# main.net
KiCad netlist of a schematic drawn in Altium Designer
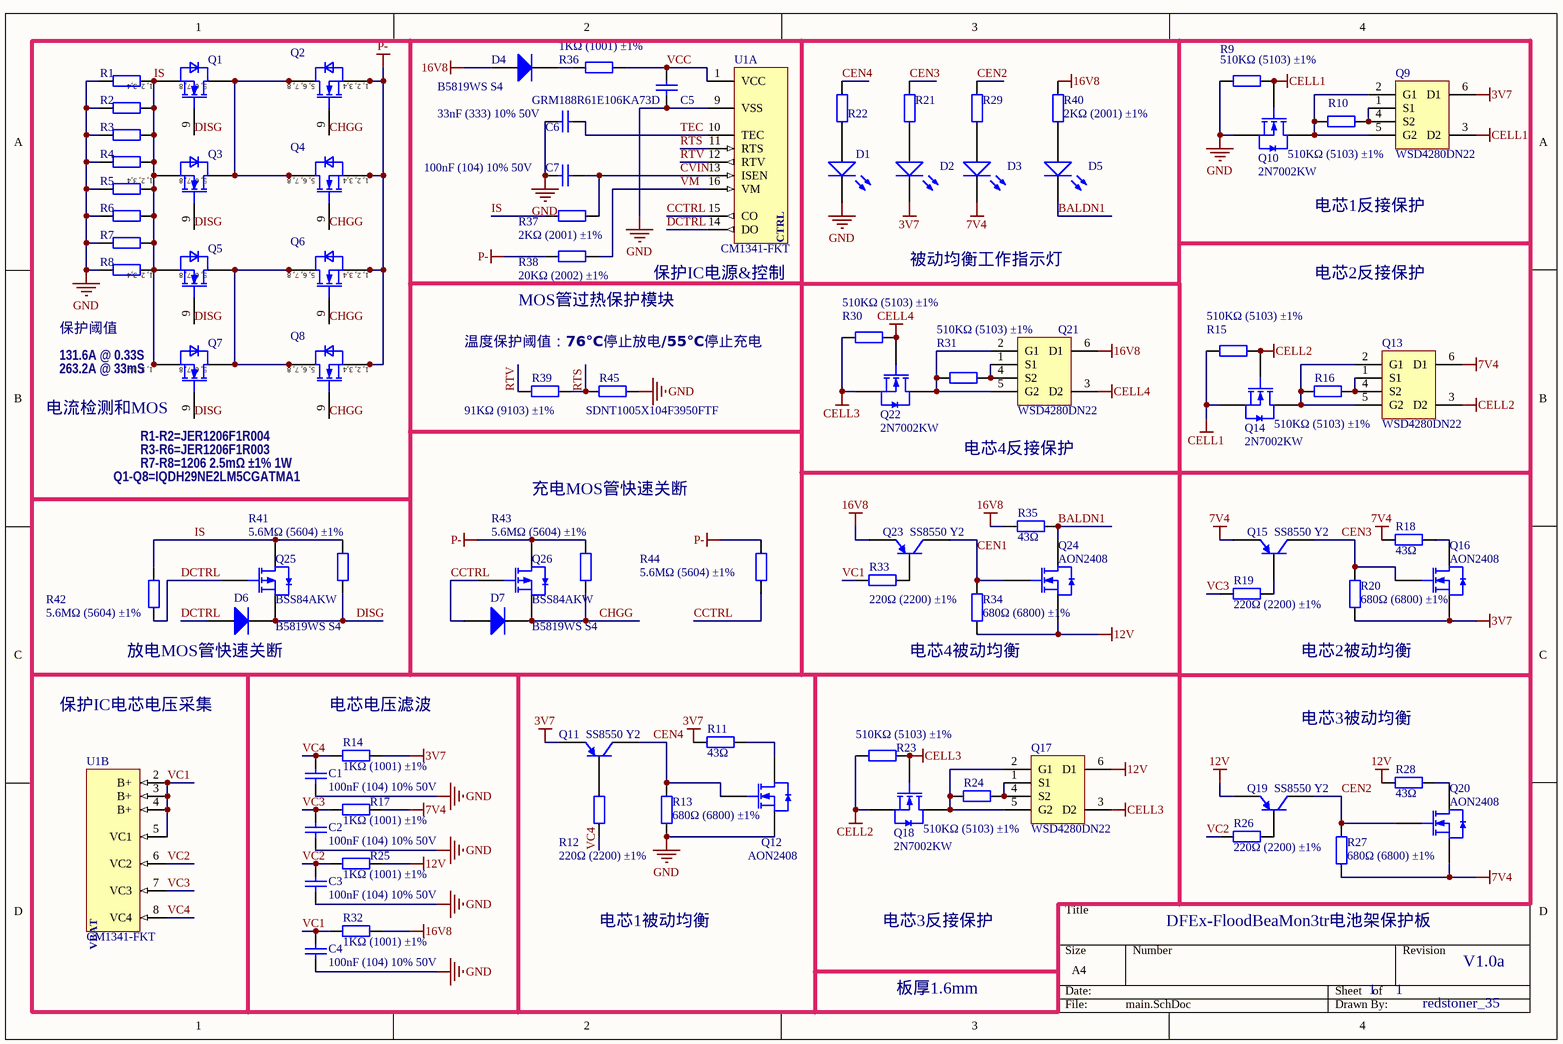
[diagram p0: main.SchDoc]

(export (version "E")
  (design (tool "Eeschema 10.0.6"))
  (components
    (comp (ref "C1")
      (value "100nF (104) 10% 50V")
      (footprint "0402_C")
      (description "贴片电容")
      (libsource (lib "Miscellaneous Devices LC") (part "0402 220nF (224) 10% 16V"))
    )
    (comp (ref "C2")
      (value "100nF (104) 10% 50V")
      (footprint "0402_C")
      (description "贴片电容")
      (libsource (lib "Miscellaneous Devices LC") (part "0402 220nF (224) 10% 16V"))
    )
    (comp (ref "C3")
      (value "100nF (104) 10% 50V")
      (footprint "0402_C")
      (description "贴片电容")
      (libsource (lib "Miscellaneous Devices LC") (part "0402 220nF (224) 10% 16V"))
    )
    (comp (ref "C4")
      (value "100nF (104) 10% 50V")
      (footprint "0402_C")
      (description "贴片电容")
      (libsource (lib "Miscellaneous Devices LC") (part "0402 220nF (224) 10% 16V"))
    )
    (comp (ref "C5")
      (value "GRM188R61E106KA73D")
      (footprint "0603_C")
      (description "0603贴片MLCC电容 10uF ±20% 25V X5R")
      (libsource (lib "Miscellaneous Devices LC") (part "0603 10uF (106) 10% 10V"))
    )
    (comp (ref "C6")
      (value "33nF (333) 10% 50V")
      (footprint "0402_C")
      (description "贴片电容")
      (libsource (lib "Miscellaneous Devices LC") (part "0402 100nF (104) 10% 16V"))
    )
    (comp (ref "C7")
      (value "100nF (104) 10% 50V")
      (footprint "0402_C")
      (description "贴片电容")
      (libsource (lib "Miscellaneous Devices LC") (part "0402 100nF (104) 10% 16V"))
    )
    (comp (ref "D1")
      (value "白灯 0603")
      (footprint "0603_LED_S1")
      (description "发光二极管")
      (libsource (lib "Miscellaneous Devices LC") (part "0603 白灯"))
    )
    (comp (ref "D2")
      (value "白灯 0603")
      (footprint "0603_LED_S1")
      (description "发光二极管")
      (libsource (lib "Miscellaneous Devices LC") (part "0603 白灯"))
    )
    (comp (ref "D3")
      (value "白灯 0603")
      (footprint "0603_LED_S1")
      (description "发光二极管")
      (libsource (lib "Miscellaneous Devices LC") (part "0603 白灯"))
    )
    (comp (ref "D4")
      (value "B5819WS S4")
      (footprint "SOD-323")
      (description "二极管")
      (libsource (lib "Miscellaneous Devices LC") (part "SOD-323 1N4148WS T4"))
    )
    (comp (ref "D5")
      (value "白灯 0603")
      (footprint "0603_LED_S1")
      (description "发光二极管")
      (libsource (lib "Miscellaneous Devices LC") (part "0603 白灯"))
    )
    (comp (ref "D6")
      (value "B5819WS S4")
      (footprint "SOD-323")
      (description "二极管")
      (libsource (lib "Miscellaneous Devices LC") (part "SOD-323 1N4148WS T4"))
    )
    (comp (ref "D7")
      (value "B5819WS S4")
      (footprint "SOD-323")
      (description "二极管")
      (libsource (lib "Miscellaneous Devices LC") (part "SOD-323 1N4148WS T4"))
    )
    (comp (ref "Q1")
      (value "IQDH29NE2LM5CG")
      (footprint "IFX-PG-WHTFN-9-2-V")
      (description "英飞凌MOSFET 25V 789A 0.2mΩ @ 10V WHTFN-9(PDFN5x6源极底置)封装")
      (fields (field (name "MANUFACTURER") "Infineon Technologies"))
      (libsource (lib "custom") (part "IQDH29NE2LM5CGSC"))
    )
    (comp (ref "Q2")
      (value "IQDH29NE2LM5CG")
      (footprint "IFX-PG-WHTFN-9-2-V")
      (description "英飞凌MOSFET 25V 789A 0.2mΩ @ 10V WHTFN-9(PDFN5x6源极底置)封装")
      (fields (field (name "MANUFACTURER") "Infineon Technologies"))
      (libsource (lib "custom") (part "IQDH29NE2LM5CGSC"))
    )
    (comp (ref "Q3")
      (value "IQDH29NE2LM5CG")
      (footprint "IFX-PG-WHTFN-9-2-V")
      (description "英飞凌MOSFET 25V 789A 0.2mΩ @ 10V WHTFN-9(PDFN5x6源极底置)封装")
      (fields (field (name "MANUFACTURER") "Infineon Technologies"))
      (libsource (lib "custom") (part "IQDH29NE2LM5CGSC"))
    )
    (comp (ref "Q4")
      (value "IQDH29NE2LM5CG")
      (footprint "IFX-PG-WHTFN-9-2-V")
      (description "英飞凌MOSFET 25V 789A 0.2mΩ @ 10V WHTFN-9(PDFN5x6源极底置)封装")
      (fields (field (name "MANUFACTURER") "Infineon Technologies"))
      (libsource (lib "custom") (part "IQDH29NE2LM5CGSC"))
    )
    (comp (ref "Q5")
      (value "IQDH29NE2LM5CG")
      (footprint "IFX-PG-WHTFN-9-2-V")
      (description "英飞凌MOSFET 25V 789A 0.2mΩ @ 10V WHTFN-9(PDFN5x6源极底置)封装")
      (fields (field (name "MANUFACTURER") "Infineon Technologies"))
      (libsource (lib "custom") (part "IQDH29NE2LM5CGSC"))
    )
    (comp (ref "Q6")
      (value "IQDH29NE2LM5CG")
      (footprint "IFX-PG-WHTFN-9-2-V")
      (description "英飞凌MOSFET 25V 789A 0.2mΩ @ 10V WHTFN-9(PDFN5x6源极底置)封装")
      (fields (field (name "MANUFACTURER") "Infineon Technologies"))
      (libsource (lib "custom") (part "IQDH29NE2LM5CGSC"))
    )
    (comp (ref "Q7")
      (value "IQDH29NE2LM5CG")
      (footprint "IFX-PG-WHTFN-9-2-V")
      (description "英飞凌MOSFET 25V 789A 0.2mΩ @ 10V WHTFN-9(PDFN5x6源极底置)封装")
      (fields (field (name "MANUFACTURER") "Infineon Technologies"))
      (libsource (lib "custom") (part "IQDH29NE2LM5CGSC"))
    )
    (comp (ref "Q8")
      (value "IQDH29NE2LM5CG")
      (footprint "IFX-PG-WHTFN-9-2-V")
      (description "英飞凌MOSFET 25V 789A 0.2mΩ @ 10V WHTFN-9(PDFN5x6源极底置)封装")
      (fields (field (name "MANUFACTURER") "Infineon Technologies"))
      (libsource (lib "custom") (part "IQDH29NE2LM5CGSC"))
    )
    (comp (ref "Q9")
      (value "WSD4280DN22")
      (footprint "UDFN-6_L2.0-W2.0-P0.65-BL_NTLUD3A50PZ")
      (description "内置肖特基二极管的双P沟道MOS -15V -4.6A 45mΩ @ 4.5V DFN2x2封装")
      (libsource (lib "custom") (part "NTLUD3A50PZ"))
    )
    (comp (ref "Q10")
      (value "2N7002KW")
      (footprint "SC70-3")
      (description "单N沟道MOSFET(场效应管)")
      (libsource (lib "Miscellaneous Devices LC") (part "2N7002 7002"))
    )
    (comp (ref "Q11")
      (value "SS8550 Y2")
      (footprint "SC70-3")
      (description "PNP三极管，SOT-323 封装")
      (libsource (lib "Miscellaneous Devices LC") (part "SOT-23 SS8550 Y2"))
    )
    (comp (ref "Q12")
      (value "AON2408")
      (footprint "PDFN-6_L2.0-W2.0-P0.65-BL-EP")
      (description "MOS(场效应管)")
      (libsource (lib "Miscellaneous Devices LC") (part "AO3400A N道沟 X0YV1T SOT-23"))
    )
    (comp (ref "Q13")
      (value "WSD4280DN22")
      (footprint "UDFN-6_L2.0-W2.0-P0.65-BL_NTLUD3A50PZ")
      (description "内置肖特基二极管的双P沟道MOS -15V -4.6A 45mΩ @ 4.5V DFN2x2封装")
      (libsource (lib "custom") (part "NTLUD3A50PZ"))
    )
    (comp (ref "Q14")
      (value "2N7002KW")
      (footprint "SC70-3")
      (description "单N沟道MOSFET(场效应管)")
      (libsource (lib "Miscellaneous Devices LC") (part "2N7002 7002"))
    )
    (comp (ref "Q15")
      (value "SS8550 Y2")
      (footprint "SC70-3")
      (description "PNP三极管，SOT-323 封装")
      (libsource (lib "Miscellaneous Devices LC") (part "SOT-23 SS8550 Y2"))
    )
    (comp (ref "Q16")
      (value "AON2408")
      (footprint "PDFN-6_L2.0-W2.0-P0.65-BL-EP")
      (description "MOS(场效应管)")
      (libsource (lib "Miscellaneous Devices LC") (part "AO3400A N道沟 X0YV1T SOT-23"))
    )
    (comp (ref "Q17")
      (value "WSD4280DN22")
      (footprint "UDFN-6_L2.0-W2.0-P0.65-BL_NTLUD3A50PZ")
      (description "内置肖特基二极管的双P沟道MOS -15V -4.6A 45mΩ @ 4.5V DFN2x2封装")
      (libsource (lib "custom") (part "NTLUD3A50PZ"))
    )
    (comp (ref "Q18")
      (value "2N7002KW")
      (footprint "SC70-3")
      (description "单N沟道MOSFET(场效应管)")
      (libsource (lib "Miscellaneous Devices LC") (part "2N7002 7002"))
    )
    (comp (ref "Q19")
      (value "SS8550 Y2")
      (footprint "SC70-3")
      (description "PNP三极管，SOT-323 封装")
      (libsource (lib "Miscellaneous Devices LC") (part "SOT-23 SS8550 Y2"))
    )
    (comp (ref "Q20")
      (value "AON2408")
      (footprint "PDFN-6_L2.0-W2.0-P0.65-BL-EP")
      (description "MOS(场效应管)")
      (libsource (lib "Miscellaneous Devices LC") (part "AO3400A N道沟 X0YV1T SOT-23"))
    )
    (comp (ref "Q21")
      (value "WSD4280DN22")
      (footprint "UDFN-6_L2.0-W2.0-P0.65-BL_NTLUD3A50PZ")
      (description "内置肖特基二极管的双P沟道MOS -15V -4.6A 45mΩ @ 4.5V DFN2x2封装")
      (libsource (lib "custom") (part "NTLUD3A50PZ"))
    )
    (comp (ref "Q22")
      (value "2N7002KW")
      (footprint "SC70-3")
      (description "单N沟道MOSFET(场效应管)")
      (libsource (lib "Miscellaneous Devices LC") (part "2N7002 7002"))
    )
    (comp (ref "Q23")
      (value "SS8550 Y2")
      (footprint "SC70-3")
      (description "PNP三极管，SOT-323 封装")
      (libsource (lib "Miscellaneous Devices LC") (part "SOT-23 SS8550 Y2"))
    )
    (comp (ref "Q24")
      (value "AON2408")
      (footprint "PDFN-6_L2.0-W2.0-P0.65-BL-EP")
      (description "MOS(场效应管)")
      (libsource (lib "Miscellaneous Devices LC") (part "AO3400A N道沟 X0YV1T SOT-23"))
    )
    (comp (ref "Q25")
      (value "BSS84AKW")
      (footprint "SC70-3")
      (description "单P沟道小信号MOSFET(场效应管)")
      (libsource (lib "Miscellaneous Devices LC") (part "SI2301CDS-T1-GE3"))
    )
    (comp (ref "Q26")
      (value "BSS84AKW")
      (footprint "SC70-3")
      (description "单P沟道小信号MOSFET(场效应管)")
      (libsource (lib "Miscellaneous Devices LC") (part "SI2301CDS-T1-GE3"))
    )
    (comp (ref "R1")
      (value "JER1206F1R004")
      (footprint "1206R")
      (description "贴片合金电流检测电阻 1206封装 4mΩ ±1% 1W")
      (fields (field (name "PUBLISHER") "Altium Limited"))
      (libsource (lib "山猫的集成库20190318") (part "Res"))
    )
    (comp (ref "R2")
      (value "JER1206F1R004")
      (footprint "1206R")
      (description "贴片合金电流检测电阻 1206封装 4mΩ ±1% 1W")
      (fields (field (name "PUBLISHER") "Altium Limited"))
      (libsource (lib "山猫的集成库20190318") (part "Res"))
    )
    (comp (ref "R3")
      (value "JER1206F1R003")
      (footprint "1206R")
      (description "贴片合金电流检测电阻 1206封装 3mΩ ±1% 1W")
      (fields (field (name "PUBLISHER") "Altium Limited"))
      (libsource (lib "山猫的集成库20190318") (part "Res"))
    )
    (comp (ref "R4")
      (value "JER1206F1R003")
      (footprint "1206R")
      (description "贴片合金电流检测电阻 1206封装 3mΩ ±1% 1W")
      (fields (field (name "PUBLISHER") "Altium Limited"))
      (libsource (lib "山猫的集成库20190318") (part "Res"))
    )
    (comp (ref "R5")
      (value "JER1206F1R003")
      (footprint "1206R")
      (description "贴片合金电流检测电阻 1206封装 3mΩ ±1% 1W")
      (fields (field (name "PUBLISHER") "Altium Limited"))
      (libsource (lib "山猫的集成库20190318") (part "Res"))
    )
    (comp (ref "R6")
      (value "JER1206F1R003")
      (footprint "1206R")
      (description "贴片合金电流检测电阻 1206封装 3mΩ ±1% 1W")
      (fields (field (name "PUBLISHER") "Altium Limited"))
      (libsource (lib "山猫的集成库20190318") (part "Res"))
    )
    (comp (ref "R7")
      (value "1206 2.5mΩ ±1% 1W")
      (footprint "1206R")
      (description "贴片合金检流电阻 1206 2.5mΩ ±1% 1W")
      (fields (field (name "PUBLISHER") "Altium Limited"))
      (libsource (lib "山猫的集成库20190318") (part "Res"))
    )
    (comp (ref "R8")
      (value "1206 2.5mΩ ±1% 1W")
      (footprint "1206R")
      (description "贴片合金检流电阻 1206 2.5mΩ ±1% 1W")
      (fields (field (name "PUBLISHER") "Altium Limited"))
      (libsource (lib "山猫的集成库20190318") (part "Res"))
    )
    (comp (ref "R9")
      (value "510KΩ (5103) ±1%")
      (footprint "0402_R")
      (description "贴片电阻")
      (libsource (lib "") (part "0402 510KΩ (5103) 1%_1"))
    )
    (comp (ref "R10")
      (value "510KΩ (5103) ±1%")
      (footprint "0402_R")
      (description "贴片电阻")
      (libsource (lib "") (part "0402 510KΩ (5103) 1%_1"))
    )
    (comp (ref "R11")
      (value "43Ω")
      (footprint "1210R")
      (description "Resistor")
      (fields (field (name "PUBLISHER") "Altium Limited"))
      (libsource (lib "山猫的集成库20190318") (part "Res"))
    )
    (comp (ref "R12")
      (value "220Ω (2200) ±1%")
      (footprint "0402_R")
      (description "贴片电阻")
      (libsource (lib "") (part "0402 220Ω (2200) 1%_1"))
    )
    (comp (ref "R13")
      (value "680Ω (6800) ±1%")
      (footprint "0402_R")
      (description "贴片电阻")
      (libsource (lib "Miscellaneous Devices LC") (part "0402 2KΩ (2001) 1%"))
    )
    (comp (ref "R14")
      (value "1KΩ (1001) ±1%")
      (footprint "0402_R")
      (description "贴片电阻")
      (libsource (lib "Miscellaneous Devices LC") (part "0402 1KΩ (1001) 1%"))
    )
    (comp (ref "R15")
      (value "510KΩ (5103) ±1%")
      (footprint "0402_R")
      (description "贴片电阻")
      (libsource (lib "Miscellaneous Devices LC") (part "0402 510KΩ (5103) 1%"))
    )
    (comp (ref "R16")
      (value "510KΩ (5103) ±1%")
      (footprint "0402_R")
      (description "贴片电阻")
      (libsource (lib "Miscellaneous Devices LC") (part "0402 510KΩ (5103) 1%"))
    )
    (comp (ref "R17")
      (value "1KΩ (1001) ±1%")
      (footprint "0402_R")
      (description "贴片电阻")
      (libsource (lib "Miscellaneous Devices LC") (part "0402 1KΩ (1001) 1%"))
    )
    (comp (ref "R18")
      (value "43Ω")
      (footprint "1210R")
      (description "Resistor")
      (fields (field (name "PUBLISHER") "Altium Limited"))
      (libsource (lib "山猫的集成库20190318") (part "Res"))
    )
    (comp (ref "R19")
      (value "220Ω (2200) ±1%")
      (footprint "0402_R")
      (description "贴片电阻")
      (libsource (lib "Miscellaneous Devices LC") (part "0402 220Ω (2200) 1%"))
    )
    (comp (ref "R20")
      (value "680Ω (6800) ±1%")
      (footprint "0402_R")
      (description "贴片电阻")
      (libsource (lib "Miscellaneous Devices LC") (part "0402 2KΩ (2001) 1%"))
    )
    (comp (ref "R21")
      (value "2KΩ (2001) ±1%")
      (footprint "0402_R")
      (description "贴片电阻")
      (libsource (lib "Miscellaneous Devices LC") (part "0402 2KΩ (2001) 1%"))
    )
    (comp (ref "R22")
      (value "2KΩ (2001) ±1%")
      (footprint "0402_R")
      (description "贴片电阻")
      (libsource (lib "Miscellaneous Devices LC") (part "0402 2KΩ (2001) 1%"))
    )
    (comp (ref "R23")
      (value "510KΩ (5103) ±1%")
      (footprint "0402_R")
      (description "贴片电阻")
      (libsource (lib "Miscellaneous Devices LC") (part "0402 510KΩ (5103) 1%"))
    )
    (comp (ref "R24")
      (value "510KΩ (5103) ±1%")
      (footprint "0402_R")
      (description "贴片电阻")
      (libsource (lib "Miscellaneous Devices LC") (part "0402 510KΩ (5103) 1%"))
    )
    (comp (ref "R25")
      (value "1KΩ (1001) ±1%")
      (footprint "0402_R")
      (description "贴片电阻")
      (libsource (lib "Miscellaneous Devices LC") (part "0402 1KΩ (1001) 1%"))
    )
    (comp (ref "R26")
      (value "220Ω (2200) ±1%")
      (footprint "0402_R")
      (description "贴片电阻")
      (libsource (lib "Miscellaneous Devices LC") (part "0402 220Ω (2200) 1%"))
    )
    (comp (ref "R27")
      (value "680Ω (6800) ±1%")
      (footprint "0402_R")
      (description "贴片电阻")
      (libsource (lib "Miscellaneous Devices LC") (part "0402 2KΩ (2001) 1%"))
    )
    (comp (ref "R28")
      (value "43Ω")
      (footprint "1210R")
      (description "Resistor")
      (fields (field (name "PUBLISHER") "Altium Limited"))
      (libsource (lib "山猫的集成库20190318") (part "Res"))
    )
    (comp (ref "R29")
      (value "2KΩ (2001) ±1%")
      (footprint "0402_R")
      (description "贴片电阻")
      (libsource (lib "Miscellaneous Devices LC") (part "0402 2KΩ (2001) 1%"))
    )
    (comp (ref "R30")
      (value "510KΩ (5103) ±1%")
      (footprint "0402_R")
      (description "贴片电阻")
      (libsource (lib "Miscellaneous Devices LC") (part "0402 510KΩ (5103) 1%"))
    )
    (comp (ref "R31")
      (value "510KΩ (5103) ±1%")
      (footprint "0402_R")
      (description "贴片电阻")
      (libsource (lib "Miscellaneous Devices LC") (part "0402 510KΩ (5103) 1%"))
    )
    (comp (ref "R32")
      (value "1KΩ (1001) ±1%")
      (footprint "0402_R")
      (description "贴片电阻")
      (libsource (lib "Miscellaneous Devices LC") (part "0402 1KΩ (1001) 1%"))
    )
    (comp (ref "R33")
      (value "220Ω (2200) ±1%")
      (footprint "0402_R")
      (description "贴片电阻")
      (libsource (lib "Miscellaneous Devices LC") (part "0402 220Ω (2200) 1%"))
    )
    (comp (ref "R34")
      (value "680Ω (6800) ±1%")
      (footprint "0402_R")
      (description "贴片电阻")
      (libsource (lib "Miscellaneous Devices LC") (part "0402 2KΩ (2001) 1%"))
    )
    (comp (ref "R35")
      (value "43Ω")
      (footprint "1210R")
      (description "Resistor")
      (fields (field (name "PUBLISHER") "Altium Limited"))
      (libsource (lib "山猫的集成库20190318") (part "Res"))
    )
    (comp (ref "R36")
      (value "1KΩ (1001) ±1%")
      (footprint "0402_R")
      (description "贴片电阻")
      (libsource (lib "Miscellaneous Devices LC") (part "0402 1KΩ (1001) 1%"))
    )
    (comp (ref "R37")
      (value "2KΩ (2001) ±1%")
      (footprint "0402_R")
      (description "贴片电阻")
      (libsource (lib "") (part "0402 2KΩ (2001) 1%_1"))
    )
    (comp (ref "R38")
      (value "20KΩ (2002) ±1%")
      (footprint "0402_R")
      (description "贴片电阻")
      (libsource (lib "Miscellaneous Devices LC") (part "0402 20KΩ (2002) 1%"))
    )
    (comp (ref "R39")
      (value "91KΩ (9103) ±1%")
      (footprint "0402_R")
      (description "贴片电阻")
      (libsource (lib "Miscellaneous Devices LC") (part "0402 100KΩ (1003) 1%"))
    )
    (comp (ref "R40")
      (value "2KΩ (2001) ±1%")
      (footprint "0402_R")
      (description "贴片电阻")
      (libsource (lib "Miscellaneous Devices LC") (part "0402 2KΩ (2001) 1%"))
    )
    (comp (ref "R41")
      (value "5.6MΩ (5604) ±1%")
      (footprint "0402_R")
      (description "贴片电阻")
      (libsource (lib "Miscellaneous Devices LC") (part "0402 1MΩ (1004) 1%"))
    )
    (comp (ref "R42")
      (value "5.6MΩ (5604) ±1%")
      (footprint "0402_R")
      (description "贴片电阻")
      (libsource (lib "Miscellaneous Devices LC") (part "0402 1MΩ (1004) 1%"))
    )
    (comp (ref "R43")
      (value "5.6MΩ (5604) ±1%")
      (footprint "0402_R")
      (description "贴片电阻")
      (libsource (lib "Miscellaneous Devices LC") (part "0402 1MΩ (1004) 1%"))
    )
    (comp (ref "R44")
      (value "5.6MΩ (5604) ±1%")
      (footprint "0402_R")
      (description "贴片电阻")
      (libsource (lib "Miscellaneous Devices LC") (part "0402 1MΩ (1004) 1%"))
    )
    (comp (ref "R45")
      (value "SDNT1005X104F3950FTF")
      (footprint "0402_R")
      (description "100KΩ (1003) ±1% B3950 NTC片式贴片热敏电阻")
      (libsource (lib "Miscellaneous Devices LC") (part "0402 100KΩ (1003) 1%"))
    )
    (comp (ref "U1")
      (value "CM1341-FKT")
      (footprint "TSSOP16-CM1341")
      (description "4串三元锂电池带均衡功能保护IC，SSOP16封装。")
      (libsource (lib "custom") (part "CM1341-FKT"))
    )
  )
  (nets
    (net (code "1") (name "/BALDN1") (class "Default")
      (node (ref "D5") (pin "K") (pinfunction "K_K") (pintype "passive"))
      (node (ref "Q24") (pin "3") (pinfunction "D_3") (pintype "passive"))
      (node (ref "R35") (pin "1") (pinfunction "1_1") (pintype "passive"))
    )
    (net (code "2") (name "/CCTRL") (class "Default")
      (node (ref "D7") (pin "1") (pinfunction "A_1") (pintype "passive"))
      (node (ref "Q26") (pin "1") (pinfunction "G_1") (pintype "passive"))
      (node (ref "R44") (pin "1") (pinfunction "1_1") (pintype "passive"))
      (node (ref "U1") (pin "15") (pinfunction "CO_15") (pintype "output"))
    )
    (net (code "3") (name "/CEN1") (class "Default")
      (node (ref "Q23") (pin "3") (pinfunction "C_3") (pintype "passive"))
      (node (ref "Q24") (pin "1") (pinfunction "G_1") (pintype "passive"))
      (node (ref "R34") (pin "2") (pinfunction "2_2") (pintype "passive"))
    )
    (net (code "4") (name "/CEN2") (class "Default")
      (node (ref "Q19") (pin "3") (pinfunction "C_3") (pintype "passive"))
      (node (ref "Q20") (pin "1") (pinfunction "G_1") (pintype "passive"))
      (node (ref "R27") (pin "2") (pinfunction "2_2") (pintype "passive"))
      (node (ref "R29") (pin "2") (pinfunction "2_2") (pintype "passive"))
    )
    (net (code "5") (name "/CEN3") (class "Default")
      (node (ref "Q15") (pin "3") (pinfunction "C_3") (pintype "passive"))
      (node (ref "Q16") (pin "1") (pinfunction "G_1") (pintype "passive"))
      (node (ref "R20") (pin "2") (pinfunction "2_2") (pintype "passive"))
      (node (ref "R21") (pin "2") (pinfunction "2_2") (pintype "passive"))
    )
    (net (code "6") (name "/CEN4") (class "Default")
      (node (ref "Q11") (pin "3") (pinfunction "C_3") (pintype "passive"))
      (node (ref "Q12") (pin "1") (pinfunction "G_1") (pintype "passive"))
      (node (ref "R13") (pin "2") (pinfunction "2_2") (pintype "passive"))
      (node (ref "R22") (pin "2") (pinfunction "2_2") (pintype "passive"))
    )
    (net (code "7") (name "/CHGG") (class "Default")
      (node (ref "D7") (pin "2") (pinfunction "K_2") (pintype "passive"))
      (node (ref "Q2") (pin "9") (pinfunction "GATE_9") (pintype "passive"))
      (node (ref "Q26") (pin "2") (pinfunction "S_2") (pintype "passive"))
      (node (ref "Q4") (pin "9") (pinfunction "GATE_9") (pintype "passive"))
      (node (ref "Q6") (pin "9") (pinfunction "GATE_9") (pintype "passive"))
      (node (ref "Q8") (pin "9") (pinfunction "GATE_9") (pintype "passive"))
      (node (ref "R43") (pin "1") (pinfunction "1_1") (pintype "passive"))
    )
    (net (code "8") (name "/CVIN") (class "Default")
      (node (ref "C7") (pin "2") (pinfunction "2_2") (pintype "passive"))
      (node (ref "R37") (pin "2") (pinfunction "2_2") (pintype "passive"))
      (node (ref "U1") (pin "13") (pinfunction "ISEN_13") (pintype "input"))
    )
    (net (code "9") (name "/DCTRL") (class "Default")
      (node (ref "D6") (pin "1") (pinfunction "A_1") (pintype "passive"))
      (node (ref "Q25") (pin "1") (pinfunction "G_1") (pintype "passive"))
      (node (ref "R42") (pin "1") (pinfunction "1_1") (pintype "passive"))
      (node (ref "U1") (pin "14") (pinfunction "DO_14") (pintype "output"))
    )
    (net (code "10") (name "/DISG") (class "Default")
      (node (ref "D6") (pin "2") (pinfunction "K_2") (pintype "passive"))
      (node (ref "Q1") (pin "9") (pinfunction "GATE_9") (pintype "passive"))
      (node (ref "Q25") (pin "2") (pinfunction "S_2") (pintype "passive"))
      (node (ref "Q3") (pin "9") (pinfunction "GATE_9") (pintype "passive"))
      (node (ref "Q5") (pin "9") (pinfunction "GATE_9") (pintype "passive"))
      (node (ref "Q7") (pin "9") (pinfunction "GATE_9") (pintype "passive"))
      (node (ref "R41") (pin "1") (pinfunction "1_1") (pintype "passive"))
    )
    (net (code "11") (name "/IS") (class "Default")
      (node (ref "Q1") (pin "1") (pinfunction "SOURCE1_1") (pintype "passive"))
      (node (ref "Q1") (pin "2") (pinfunction "SOURCE2_2") (pintype "passive"))
      (node (ref "Q1") (pin "3") (pinfunction "SOURCE3_3") (pintype "passive"))
      (node (ref "Q1") (pin "4") (pinfunction "SOURCE4_4") (pintype "passive"))
      (node (ref "Q25") (pin "3") (pinfunction "D_3") (pintype "passive"))
      (node (ref "Q3") (pin "1") (pinfunction "SOURCE1_1") (pintype "passive"))
      (node (ref "Q3") (pin "2") (pinfunction "SOURCE2_2") (pintype "passive"))
      (node (ref "Q3") (pin "3") (pinfunction "SOURCE3_3") (pintype "passive"))
      (node (ref "Q3") (pin "4") (pinfunction "SOURCE4_4") (pintype "passive"))
      (node (ref "Q5") (pin "1") (pinfunction "SOURCE1_1") (pintype "passive"))
      (node (ref "Q5") (pin "2") (pinfunction "SOURCE2_2") (pintype "passive"))
      (node (ref "Q5") (pin "3") (pinfunction "SOURCE3_3") (pintype "passive"))
      (node (ref "Q5") (pin "4") (pinfunction "SOURCE4_4") (pintype "passive"))
      (node (ref "Q7") (pin "1") (pinfunction "SOURCE1_1") (pintype "passive"))
      (node (ref "Q7") (pin "2") (pinfunction "SOURCE2_2") (pintype "passive"))
      (node (ref "Q7") (pin "3") (pinfunction "SOURCE3_3") (pintype "passive"))
      (node (ref "Q7") (pin "4") (pinfunction "SOURCE4_4") (pintype "passive"))
      (node (ref "R1") (pin "1") (pinfunction "1_1") (pintype "passive"))
      (node (ref "R2") (pin "1") (pinfunction "1_1") (pintype "passive"))
      (node (ref "R3") (pin "1") (pinfunction "1_1") (pintype "passive"))
      (node (ref "R37") (pin "1") (pinfunction "1_1") (pintype "passive"))
      (node (ref "R4") (pin "1") (pinfunction "1_1") (pintype "passive"))
      (node (ref "R41") (pin "2") (pinfunction "2_2") (pintype "passive"))
      (node (ref "R42") (pin "2") (pinfunction "2_2") (pintype "passive"))
      (node (ref "R5") (pin "1") (pinfunction "1_1") (pintype "passive"))
      (node (ref "R6") (pin "1") (pinfunction "1_1") (pintype "passive"))
      (node (ref "R7") (pin "1") (pinfunction "1_1") (pintype "passive"))
      (node (ref "R8") (pin "1") (pinfunction "1_1") (pintype "passive"))
    )
    (net (code "12") (name "/RTS") (class "Default")
      (node (ref "R39") (pin "1") (pinfunction "1_1") (pintype "passive"))
      (node (ref "R45") (pin "2") (pinfunction "2_2") (pintype "passive"))
      (node (ref "U1") (pin "11") (pinfunction "RTS_11") (pintype "input"))
    )
    (net (code "13") (name "/RTV") (class "Default")
      (node (ref "R39") (pin "2") (pinfunction "2_2") (pintype "passive"))
      (node (ref "U1") (pin "12") (pinfunction "RTV_12") (pintype "output"))
    )
    (net (code "14") (name "/TEC") (class "Default")
      (node (ref "C6") (pin "2") (pinfunction "2_2") (pintype "passive"))
      (node (ref "U1") (pin "10") (pinfunction "TEC_10") (pintype "passive"))
    )
    (net (code "15") (name "/VC1") (class "Default")
      (node (ref "C4") (pin "2") (pinfunction "2_2") (pintype "passive"))
      (node (ref "R32") (pin "1") (pinfunction "1_1") (pintype "passive"))
      (node (ref "R33") (pin "1") (pinfunction "1_1") (pintype "passive"))
      (node (ref "U1") (pin "2") (pinfunction "B+_2") (pintype "input"))
      (node (ref "U1") (pin "3") (pinfunction "B+_3") (pintype "input"))
      (node (ref "U1") (pin "4") (pinfunction "B+_4") (pintype "input"))
      (node (ref "U1") (pin "5") (pinfunction "VC1_5") (pintype "input"))
    )
    (net (code "16") (name "/VC2") (class "Default")
      (node (ref "C3") (pin "2") (pinfunction "2_2") (pintype "passive"))
      (node (ref "R25") (pin "1") (pinfunction "1_1") (pintype "passive"))
      (node (ref "R26") (pin "1") (pinfunction "1_1") (pintype "passive"))
      (node (ref "U1") (pin "6") (pinfunction "VC2_6") (pintype "input"))
    )
    (net (code "17") (name "/VC3") (class "Default")
      (node (ref "C2") (pin "2") (pinfunction "2_2") (pintype "passive"))
      (node (ref "R17") (pin "1") (pinfunction "1_1") (pintype "passive"))
      (node (ref "R19") (pin "1") (pinfunction "1_1") (pintype "passive"))
      (node (ref "U1") (pin "7") (pinfunction "VC3_7") (pintype "input"))
    )
    (net (code "18") (name "/VC4") (class "Default")
      (node (ref "C1") (pin "2") (pinfunction "2_2") (pintype "passive"))
      (node (ref "R12") (pin "1") (pinfunction "1_1") (pintype "passive"))
      (node (ref "R14") (pin "1") (pinfunction "1_1") (pintype "passive"))
      (node (ref "U1") (pin "8") (pinfunction "VC4_8") (pintype "input"))
    )
    (net (code "19") (name "/VCC") (class "Default")
      (node (ref "C5") (pin "2") (pinfunction "2_2") (pintype "passive"))
      (node (ref "R36") (pin "2") (pinfunction "2_2") (pintype "passive"))
      (node (ref "U1") (pin "1") (pinfunction "VCC_1") (pintype "power_in"))
    )
    (net (code "20") (name "/VM") (class "Default")
      (node (ref "R38") (pin "2") (pinfunction "2_2") (pintype "passive"))
      (node (ref "U1") (pin "16") (pinfunction "VM_16") (pintype "input"))
    )
    (net (code "21") (name "3V7") (class "Default")
      (node (ref "D2") (pin "K") (pinfunction "K_K") (pintype "passive"))
      (node (ref "Q11") (pin "2") (pinfunction "E_2") (pintype "passive"))
      (node (ref "Q16") (pin "2") (pinfunction "S_2") (pintype "passive"))
      (node (ref "Q9") (pin "6") (pinfunction "D1_6") (pintype "passive"))
      (node (ref "R11") (pin "2") (pinfunction "2_2") (pintype "passive"))
      (node (ref "R14") (pin "2") (pinfunction "2_2") (pintype "passive"))
      (node (ref "R20") (pin "1") (pinfunction "1_1") (pintype "passive"))
    )
    (net (code "22") (name "7V4") (class "Default")
      (node (ref "D3") (pin "K") (pinfunction "K_K") (pintype "passive"))
      (node (ref "Q13") (pin "6") (pinfunction "D1_6") (pintype "passive"))
      (node (ref "Q15") (pin "2") (pinfunction "E_2") (pintype "passive"))
      (node (ref "Q20") (pin "2") (pinfunction "S_2") (pintype "passive"))
      (node (ref "R17") (pin "2") (pinfunction "2_2") (pintype "passive"))
      (node (ref "R18") (pin "2") (pinfunction "2_2") (pintype "passive"))
      (node (ref "R27") (pin "1") (pinfunction "1_1") (pintype "passive"))
    )
    (net (code "23") (name "12V") (class "Default")
      (node (ref "Q17") (pin "6") (pinfunction "D1_6") (pintype "passive"))
      (node (ref "Q19") (pin "2") (pinfunction "E_2") (pintype "passive"))
      (node (ref "Q24") (pin "2") (pinfunction "S_2") (pintype "passive"))
      (node (ref "R25") (pin "2") (pinfunction "2_2") (pintype "passive"))
      (node (ref "R28") (pin "2") (pinfunction "2_2") (pintype "passive"))
      (node (ref "R34") (pin "1") (pinfunction "1_1") (pintype "passive"))
    )
    (net (code "24") (name "16V8") (class "Default")
      (node (ref "D4") (pin "1") (pinfunction "A_1") (pintype "passive"))
      (node (ref "Q21") (pin "6") (pinfunction "D1_6") (pintype "passive"))
      (node (ref "Q23") (pin "2") (pinfunction "E_2") (pintype "passive"))
      (node (ref "R32") (pin "2") (pinfunction "2_2") (pintype "passive"))
      (node (ref "R35") (pin "2") (pinfunction "2_2") (pintype "passive"))
      (node (ref "R40") (pin "2") (pinfunction "2_2") (pintype "passive"))
    )
    (net (code "25") (name "CELL1") (class "Default")
      (node (ref "Q10") (pin "1") (pinfunction "G_1") (pintype "passive"))
      (node (ref "Q14") (pin "2") (pinfunction "S_2") (pintype "passive"))
      (node (ref "Q9") (pin "3") (pinfunction "D2_3") (pintype "passive"))
      (node (ref "R15") (pin "1") (pinfunction "1_1") (pintype "passive"))
      (node (ref "R9") (pin "1") (pinfunction "1_1") (pintype "passive"))
    )
    (net (code "26") (name "CELL2") (class "Default")
      (node (ref "Q13") (pin "3") (pinfunction "D2_3") (pintype "passive"))
      (node (ref "Q14") (pin "1") (pinfunction "G_1") (pintype "passive"))
      (node (ref "Q18") (pin "2") (pinfunction "S_2") (pintype "passive"))
      (node (ref "R15") (pin "2") (pinfunction "2_2") (pintype "passive"))
      (node (ref "R23") (pin "1") (pinfunction "1_1") (pintype "passive"))
    )
    (net (code "27") (name "CELL3") (class "Default")
      (node (ref "Q17") (pin "3") (pinfunction "D2_3") (pintype "passive"))
      (node (ref "Q18") (pin "1") (pinfunction "G_1") (pintype "passive"))
      (node (ref "Q22") (pin "2") (pinfunction "S_2") (pintype "passive"))
      (node (ref "R23") (pin "2") (pinfunction "2_2") (pintype "passive"))
      (node (ref "R30") (pin "1") (pinfunction "1_1") (pintype "passive"))
    )
    (net (code "28") (name "CELL4") (class "Default")
      (node (ref "Q21") (pin "3") (pinfunction "D2_3") (pintype "passive"))
      (node (ref "Q22") (pin "1") (pinfunction "G_1") (pintype "passive"))
      (node (ref "R30") (pin "2") (pinfunction "2_2") (pintype "passive"))
    )
    (net (code "29") (name "GND") (class "Default")
      (node (ref "C1") (pin "1") (pinfunction "1_1") (pintype "passive"))
      (node (ref "C2") (pin "1") (pinfunction "1_1") (pintype "passive"))
      (node (ref "C3") (pin "1") (pinfunction "1_1") (pintype "passive"))
      (node (ref "C4") (pin "1") (pinfunction "1_1") (pintype "passive"))
      (node (ref "C5") (pin "1") (pinfunction "1_1") (pintype "passive"))
      (node (ref "C6") (pin "1") (pinfunction "1_1") (pintype "passive"))
      (node (ref "C7") (pin "1") (pinfunction "1_1") (pintype "passive"))
      (node (ref "D1") (pin "K") (pinfunction "K_K") (pintype "passive"))
      (node (ref "Q10") (pin "2") (pinfunction "S_2") (pintype "passive"))
      (node (ref "Q12") (pin "2") (pinfunction "S_2") (pintype "passive"))
      (node (ref "R1") (pin "2") (pinfunction "2_2") (pintype "passive"))
      (node (ref "R13") (pin "1") (pinfunction "1_1") (pintype "passive"))
      (node (ref "R2") (pin "2") (pinfunction "2_2") (pintype "passive"))
      (node (ref "R3") (pin "2") (pinfunction "2_2") (pintype "passive"))
      (node (ref "R4") (pin "2") (pinfunction "2_2") (pintype "passive"))
      (node (ref "R45") (pin "1") (pinfunction "1_1") (pintype "passive"))
      (node (ref "R5") (pin "2") (pinfunction "2_2") (pintype "passive"))
      (node (ref "R6") (pin "2") (pinfunction "2_2") (pintype "passive"))
      (node (ref "R7") (pin "2") (pinfunction "2_2") (pintype "passive"))
      (node (ref "R8") (pin "2") (pinfunction "2_2") (pintype "passive"))
      (node (ref "R9") (pin "2") (pinfunction "2_2") (pintype "passive"))
      (node (ref "U1") (pin "9") (pinfunction "VSS_9") (pintype "power_in"))
    )
    (net (code "30") (name "Net-(D1-PadA)") (class "Default")
      (node (ref "D1") (pin "A") (pinfunction "A_A") (pintype "passive"))
      (node (ref "R22") (pin "1") (pinfunction "1_1") (pintype "passive"))
    )
    (net (code "31") (name "Net-(D2-PadA)") (class "Default")
      (node (ref "D2") (pin "A") (pinfunction "A_A") (pintype "passive"))
      (node (ref "R21") (pin "1") (pinfunction "1_1") (pintype "passive"))
    )
    (net (code "32") (name "Net-(D3-PadA)") (class "Default")
      (node (ref "D3") (pin "A") (pinfunction "A_A") (pintype "passive"))
      (node (ref "R29") (pin "1") (pinfunction "1_1") (pintype "passive"))
    )
    (net (code "33") (name "Net-(D4-K)") (class "Default")
      (node (ref "D4") (pin "2") (pinfunction "K_2") (pintype "passive"))
      (node (ref "R36") (pin "1") (pinfunction "1_1") (pintype "passive"))
    )
    (net (code "34") (name "Net-(D5-PadA)") (class "Default")
      (node (ref "D5") (pin "A") (pinfunction "A_A") (pintype "passive"))
      (node (ref "R40") (pin "1") (pinfunction "1_1") (pintype "passive"))
    )
    (net (code "35") (name "Net-(Q1-DRAIN1)") (class "Default")
      (node (ref "Q1") (pin "5") (pinfunction "DRAIN1_5") (pintype "passive"))
      (node (ref "Q1") (pin "6") (pinfunction "DRAIN2_6") (pintype "passive"))
      (node (ref "Q1") (pin "7") (pinfunction "DRAIN3_7") (pintype "passive"))
      (node (ref "Q1") (pin "8") (pinfunction "DRAIN4_8") (pintype "passive"))
      (node (ref "Q2") (pin "5") (pinfunction "DRAIN1_5") (pintype "passive"))
      (node (ref "Q2") (pin "6") (pinfunction "DRAIN2_6") (pintype "passive"))
      (node (ref "Q2") (pin "7") (pinfunction "DRAIN3_7") (pintype "passive"))
      (node (ref "Q2") (pin "8") (pinfunction "DRAIN4_8") (pintype "passive"))
      (node (ref "Q3") (pin "5") (pinfunction "DRAIN1_5") (pintype "passive"))
      (node (ref "Q3") (pin "6") (pinfunction "DRAIN2_6") (pintype "passive"))
      (node (ref "Q3") (pin "7") (pinfunction "DRAIN3_7") (pintype "passive"))
      (node (ref "Q3") (pin "8") (pinfunction "DRAIN4_8") (pintype "passive"))
      (node (ref "Q4") (pin "5") (pinfunction "DRAIN1_5") (pintype "passive"))
      (node (ref "Q4") (pin "6") (pinfunction "DRAIN2_6") (pintype "passive"))
      (node (ref "Q4") (pin "7") (pinfunction "DRAIN3_7") (pintype "passive"))
      (node (ref "Q4") (pin "8") (pinfunction "DRAIN4_8") (pintype "passive"))
    )
    (net (code "36") (name "Net-(Q5-DRAIN1)") (class "Default")
      (node (ref "Q5") (pin "5") (pinfunction "DRAIN1_5") (pintype "passive"))
      (node (ref "Q5") (pin "6") (pinfunction "DRAIN2_6") (pintype "passive"))
      (node (ref "Q5") (pin "7") (pinfunction "DRAIN3_7") (pintype "passive"))
      (node (ref "Q5") (pin "8") (pinfunction "DRAIN4_8") (pintype "passive"))
      (node (ref "Q6") (pin "5") (pinfunction "DRAIN1_5") (pintype "passive"))
      (node (ref "Q6") (pin "6") (pinfunction "DRAIN2_6") (pintype "passive"))
      (node (ref "Q6") (pin "7") (pinfunction "DRAIN3_7") (pintype "passive"))
      (node (ref "Q6") (pin "8") (pinfunction "DRAIN4_8") (pintype "passive"))
      (node (ref "Q7") (pin "5") (pinfunction "DRAIN1_5") (pintype "passive"))
      (node (ref "Q7") (pin "6") (pinfunction "DRAIN2_6") (pintype "passive"))
      (node (ref "Q7") (pin "7") (pinfunction "DRAIN3_7") (pintype "passive"))
      (node (ref "Q7") (pin "8") (pinfunction "DRAIN4_8") (pintype "passive"))
      (node (ref "Q8") (pin "5") (pinfunction "DRAIN1_5") (pintype "passive"))
      (node (ref "Q8") (pin "6") (pinfunction "DRAIN2_6") (pintype "passive"))
      (node (ref "Q8") (pin "7") (pinfunction "DRAIN3_7") (pintype "passive"))
      (node (ref "Q8") (pin "8") (pinfunction "DRAIN4_8") (pintype "passive"))
    )
    (net (code "37") (name "Net-(Q9-S1)") (class "Default")
      (node (ref "Q9") (pin "1") (pinfunction "S1_1") (pintype "passive"))
      (node (ref "Q9") (pin "4") (pinfunction "S2_4") (pintype "passive"))
      (node (ref "R10") (pin "1") (pinfunction "1_1") (pintype "passive"))
    )
    (net (code "38") (name "Net-(Q10-D)") (class "Default")
      (node (ref "Q10") (pin "3") (pinfunction "D_3") (pintype "passive"))
      (node (ref "Q9") (pin "2") (pinfunction "G1_2") (pintype "passive"))
      (node (ref "Q9") (pin "5") (pinfunction "G2_5") (pintype "passive"))
      (node (ref "R10") (pin "2") (pinfunction "2_2") (pintype "passive"))
    )
    (net (code "39") (name "Net-(Q11-B)") (class "Default")
      (node (ref "Q11") (pin "1") (pinfunction "B_1") (pintype "passive"))
      (node (ref "R12") (pin "2") (pinfunction "2_2") (pintype "passive"))
    )
    (net (code "40") (name "Net-(Q12-D)") (class "Default")
      (node (ref "Q12") (pin "3") (pinfunction "D_3") (pintype "passive"))
      (node (ref "R11") (pin "1") (pinfunction "1_1") (pintype "passive"))
    )
    (net (code "41") (name "Net-(Q13-G1)") (class "Default")
      (node (ref "Q13") (pin "2") (pinfunction "G1_2") (pintype "passive"))
      (node (ref "Q13") (pin "5") (pinfunction "G2_5") (pintype "passive"))
      (node (ref "Q14") (pin "3") (pinfunction "D_3") (pintype "passive"))
      (node (ref "R16") (pin "1") (pinfunction "1_1") (pintype "passive"))
    )
    (net (code "42") (name "Net-(Q13-S1)") (class "Default")
      (node (ref "Q13") (pin "1") (pinfunction "S1_1") (pintype "passive"))
      (node (ref "Q13") (pin "4") (pinfunction "S2_4") (pintype "passive"))
      (node (ref "R16") (pin "2") (pinfunction "2_2") (pintype "passive"))
    )
    (net (code "43") (name "Net-(Q15-B)") (class "Default")
      (node (ref "Q15") (pin "1") (pinfunction "B_1") (pintype "passive"))
      (node (ref "R19") (pin "2") (pinfunction "2_2") (pintype "passive"))
    )
    (net (code "44") (name "Net-(Q16-D)") (class "Default")
      (node (ref "Q16") (pin "3") (pinfunction "D_3") (pintype "passive"))
      (node (ref "R18") (pin "1") (pinfunction "1_1") (pintype "passive"))
    )
    (net (code "45") (name "Net-(Q17-G1)") (class "Default")
      (node (ref "Q17") (pin "2") (pinfunction "G1_2") (pintype "passive"))
      (node (ref "Q17") (pin "5") (pinfunction "G2_5") (pintype "passive"))
      (node (ref "Q18") (pin "3") (pinfunction "D_3") (pintype "passive"))
      (node (ref "R24") (pin "1") (pinfunction "1_1") (pintype "passive"))
    )
    (net (code "46") (name "Net-(Q17-S1)") (class "Default")
      (node (ref "Q17") (pin "1") (pinfunction "S1_1") (pintype "passive"))
      (node (ref "Q17") (pin "4") (pinfunction "S2_4") (pintype "passive"))
      (node (ref "R24") (pin "2") (pinfunction "2_2") (pintype "passive"))
    )
    (net (code "47") (name "Net-(Q19-B)") (class "Default")
      (node (ref "Q19") (pin "1") (pinfunction "B_1") (pintype "passive"))
      (node (ref "R26") (pin "2") (pinfunction "2_2") (pintype "passive"))
    )
    (net (code "48") (name "Net-(Q20-D)") (class "Default")
      (node (ref "Q20") (pin "3") (pinfunction "D_3") (pintype "passive"))
      (node (ref "R28") (pin "1") (pinfunction "1_1") (pintype "passive"))
    )
    (net (code "49") (name "Net-(Q21-G1)") (class "Default")
      (node (ref "Q21") (pin "2") (pinfunction "G1_2") (pintype "passive"))
      (node (ref "Q21") (pin "5") (pinfunction "G2_5") (pintype "passive"))
      (node (ref "Q22") (pin "3") (pinfunction "D_3") (pintype "passive"))
      (node (ref "R31") (pin "1") (pinfunction "1_1") (pintype "passive"))
    )
    (net (code "50") (name "Net-(Q21-S1)") (class "Default")
      (node (ref "Q21") (pin "1") (pinfunction "S1_1") (pintype "passive"))
      (node (ref "Q21") (pin "4") (pinfunction "S2_4") (pintype "passive"))
      (node (ref "R31") (pin "2") (pinfunction "2_2") (pintype "passive"))
    )
    (net (code "51") (name "Net-(Q23-B)") (class "Default")
      (node (ref "Q23") (pin "1") (pinfunction "B_1") (pintype "passive"))
      (node (ref "R33") (pin "2") (pinfunction "2_2") (pintype "passive"))
    )
    (net (code "52") (name "P-") (class "Default")
      (node (ref "Q2") (pin "1") (pinfunction "SOURCE1_1") (pintype "passive"))
      (node (ref "Q2") (pin "2") (pinfunction "SOURCE2_2") (pintype "passive"))
      (node (ref "Q2") (pin "3") (pinfunction "SOURCE3_3") (pintype "passive"))
      (node (ref "Q2") (pin "4") (pinfunction "SOURCE4_4") (pintype "passive"))
      (node (ref "Q26") (pin "3") (pinfunction "D_3") (pintype "passive"))
      (node (ref "Q4") (pin "1") (pinfunction "SOURCE1_1") (pintype "passive"))
      (node (ref "Q4") (pin "2") (pinfunction "SOURCE2_2") (pintype "passive"))
      (node (ref "Q4") (pin "3") (pinfunction "SOURCE3_3") (pintype "passive"))
      (node (ref "Q4") (pin "4") (pinfunction "SOURCE4_4") (pintype "passive"))
      (node (ref "Q6") (pin "1") (pinfunction "SOURCE1_1") (pintype "passive"))
      (node (ref "Q6") (pin "2") (pinfunction "SOURCE2_2") (pintype "passive"))
      (node (ref "Q6") (pin "3") (pinfunction "SOURCE3_3") (pintype "passive"))
      (node (ref "Q6") (pin "4") (pinfunction "SOURCE4_4") (pintype "passive"))
      (node (ref "Q8") (pin "1") (pinfunction "SOURCE1_1") (pintype "passive"))
      (node (ref "Q8") (pin "2") (pinfunction "SOURCE2_2") (pintype "passive"))
      (node (ref "Q8") (pin "3") (pinfunction "SOURCE3_3") (pintype "passive"))
      (node (ref "Q8") (pin "4") (pinfunction "SOURCE4_4") (pintype "passive"))
      (node (ref "R38") (pin "1") (pinfunction "1_1") (pintype "passive"))
      (node (ref "R43") (pin "2") (pinfunction "2_2") (pintype "passive"))
      (node (ref "R44") (pin "2") (pinfunction "2_2") (pintype "passive"))
    )
  )
)
